# dali_phy_blk.net
KiCad netlist of a schematic drawn in Altium Designer
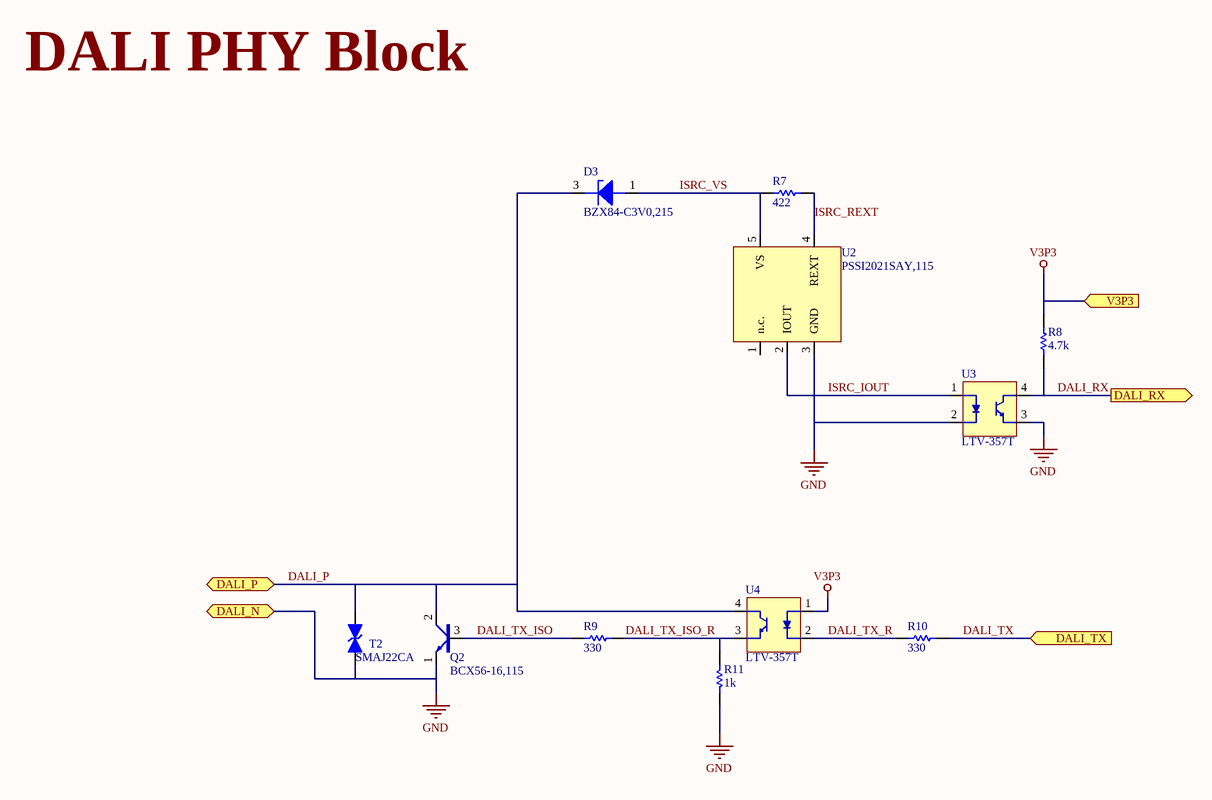
[diagram p0: dali_phy_blk.SchDoc]

(export (version "E")
  (design (tool "Eeschema 10.0.6"))
  (components
    (comp (ref "D3")
      (value "BZX84-C3V0,215")
      (footprint "SOT-23(TO-236AB)")
      (description "DIODE ZENER 3V 250MW TO236AB")
      (fields
        (field (name "MANUFACTURER") "NXP Semiconductors")
        (field (name "TOLERANCE") "±5%")
        (field (name "MANUFACTURER PART NUMBER") "BZX84-C3V0,215")
      )
      (libsource (lib "wilamp_st") (part "BZX84-C3V0,215"))
    )
    (comp (ref "Q2")
      (value "BCX56-16,115")
      (footprint "SOT 89-3")
      (description "TRANS NPN MED 1A 80V SOT89")
      (fields
        (field (name "MANUFACTURER") "NXP Semiconductors")
        (field (name "MANUFACTURER PART NUMBER") "BCX56-16,115")
      )
      (libsource (lib "WiLamp") (part "BCX56-16,115"))
    )
    (comp (ref "R7")
      (value "422")
      (footprint "R0402")
      (description "RES SMD 422 OHM 1% 1/10W 0402")
      (fields (field (name "MPN") "ERJ-2RKF4220X"))
      (libsource (lib "Res") (part "ERJ-2RKF4220X"))
    )
    (comp (ref "R8")
      (value "4.7k")
      (footprint "R0402")
      (description "RES SMD 4.7K OHM 1% 1/16W 0402")
      (fields (field (name "MPN") "RT0402FRE074K7L"))
      (libsource (lib "Res") (part "RT0402FRE074K7L"))
    )
    (comp (ref "R9")
      (value "330")
      (footprint "R0402")
      (description "RES SMD 330 OHM 1% 1/16W 0402")
      (fields (field (name "MPN") "CRCW0402330RFKED"))
      (libsource (lib "Res") (part "CRCW0402330RFKED"))
    )
    (comp (ref "R10")
      (value "330")
      (footprint "R0402")
      (description "RES SMD 330 OHM 1% 1/16W 0402")
      (fields (field (name "MPN") "CRCW0402330RFKED"))
      (libsource (lib "Res") (part "CRCW0402330RFKED"))
    )
    (comp (ref "R11")
      (value "1k")
      (footprint "R0402")
      (description "RES SMD 1K OHM 1% 1/10W 0402")
      (fields (field (name "MPN") "MCS04020C1001FE000"))
      (libsource (lib "Res") (part "MCS04020C1001FE000"))
    )
    (comp (ref "T2")
      (value "SMAJ22CA")
      (footprint "DO-214AC")
      (description "TVS Diodes - Transient Voltage Suppressors 22Vr 400W 11.3A 5% BiDirectional")
      (fields (field (name "MPN") "SMAJ22CA"))
      (libsource (lib "Diode") (part "SMAJ22CA"))
    )
    (comp (ref "U2")
      (value "PSSI2021SAY,115")
      (footprint "SOT353")
      (description "NXP - PSSI2021SAY,115 - IC, CURRENT REGULATOR, 75V, 50MA, 5-SOT-353, FULL REEL")
      (fields (field (name "MANUFACTURER") "NXP") (field (name "MANUFACTURER PART NUMBER") "PSSI2021SAY,115"))
      (libsource (lib "WI4B") (part "PSSI2021SAY,115"))
    )
    (comp (ref "U3")
      (value "LTV-357T")
      (footprint "4SMD(gull wing)")
      (description "OPTOISOLATOR 3.75KV TRANS 4-SOP")
      (fields (field (name "MPN") "LTV-357T"))
      (libsource (lib "") (part "LTV-357T_1"))
    )
    (comp (ref "U4")
      (value "LTV-357T")
      (footprint "4SMD(gull wing)")
      (description "OPTOISOLATOR 3.75KV TRANS 4-SOP")
      (fields (field (name "MPN") "LTV-357T"))
      (libsource (lib "IC") (part "LTV-357T"))
    )
  )
  (nets
    (net (code "1") (name "/DALI_P") (class "Default")
      (node (ref "D3") (pin "3") (pinfunction "K_3") (pintype "passive"))
      (node (ref "Q2") (pin "2") (pinfunction "collector_2") (pintype "passive"))
      (node (ref "T2") (pin "1") (pinfunction "A_1") (pintype "passive"))
      (node (ref "U4") (pin "4") (pinfunction "Collector_4") (pintype "passive"))
    )
    (net (code "2") (name "/DALI_RX") (class "Default")
      (node (ref "R8") (pin "1") (pinfunction "1_1") (pintype "passive"))
      (node (ref "U3") (pin "4") (pinfunction "Collector_4") (pintype "passive"))
    )
    (net (code "3") (name "/DALI_TX") (class "Default")
      (node (ref "R10") (pin "2") (pinfunction "2_2") (pintype "passive"))
    )
    (net (code "4") (name "/DALI_TX_ISO") (class "Default")
      (node (ref "Q2") (pin "3") (pinfunction "base_3") (pintype "passive"))
      (node (ref "R9") (pin "1") (pinfunction "1_1") (pintype "passive"))
    )
    (net (code "5") (name "/DALI_TX_ISO_R") (class "Default")
      (node (ref "R11") (pin "2") (pinfunction "2_2") (pintype "passive"))
      (node (ref "R9") (pin "2") (pinfunction "2_2") (pintype "passive"))
      (node (ref "U4") (pin "3") (pinfunction "Emitter_3") (pintype "passive"))
    )
    (net (code "6") (name "/DALI_TX_R") (class "Default")
      (node (ref "R10") (pin "1") (pinfunction "1_1") (pintype "passive"))
      (node (ref "U4") (pin "2") (pinfunction "Cathode_2") (pintype "passive"))
    )
    (net (code "7") (name "/ISRC_IOUT") (class "Default")
      (node (ref "U2") (pin "2") (pinfunction "IOUT_2") (pintype "passive"))
      (node (ref "U3") (pin "1") (pinfunction "Anode_1") (pintype "passive"))
    )
    (net (code "8") (name "/ISRC_REXT") (class "Default")
      (node (ref "R7") (pin "2") (pinfunction "2_2") (pintype "passive"))
      (node (ref "U2") (pin "4") (pinfunction "REXT_4") (pintype "passive"))
    )
    (net (code "9") (name "/ISRC_VS") (class "Default")
      (node (ref "D3") (pin "1") (pinfunction "A_1") (pintype "passive"))
      (node (ref "R7") (pin "1") (pinfunction "1_1") (pintype "passive"))
      (node (ref "U2") (pin "5") (pinfunction "VS_5") (pintype "passive"))
    )
    (net (code "10") (name "GND") (class "Default")
      (node (ref "Q2") (pin "1") (pinfunction "emitter_1") (pintype "passive"))
      (node (ref "R11") (pin "1") (pinfunction "1_1") (pintype "passive"))
      (node (ref "T2") (pin "2") (pinfunction "K_2") (pintype "passive"))
      (node (ref "U2") (pin "3") (pinfunction "GND_3") (pintype "passive"))
      (node (ref "U3") (pin "2") (pinfunction "Cathode_2") (pintype "passive"))
      (node (ref "U3") (pin "3") (pinfunction "Emitter_3") (pintype "passive"))
    )
    (net (code "11") (name "V3P3") (class "Default")
      (node (ref "R8") (pin "2") (pinfunction "2_2") (pintype "passive"))
      (node (ref "U4") (pin "1") (pinfunction "Anode_1") (pintype "passive"))
    )
    (net (code "12") (name "unconnected-(U2-n.c.-Pad1)") (class "Default")
      (node (ref "U2") (pin "1") (pinfunction "n.c._1") (pintype "passive"))
    )
  )
)
